# SCH_NeoGeo_chip_adapter_board_2026-08-28.net
KiCad netlist of a schematic drawn in EasyEDA
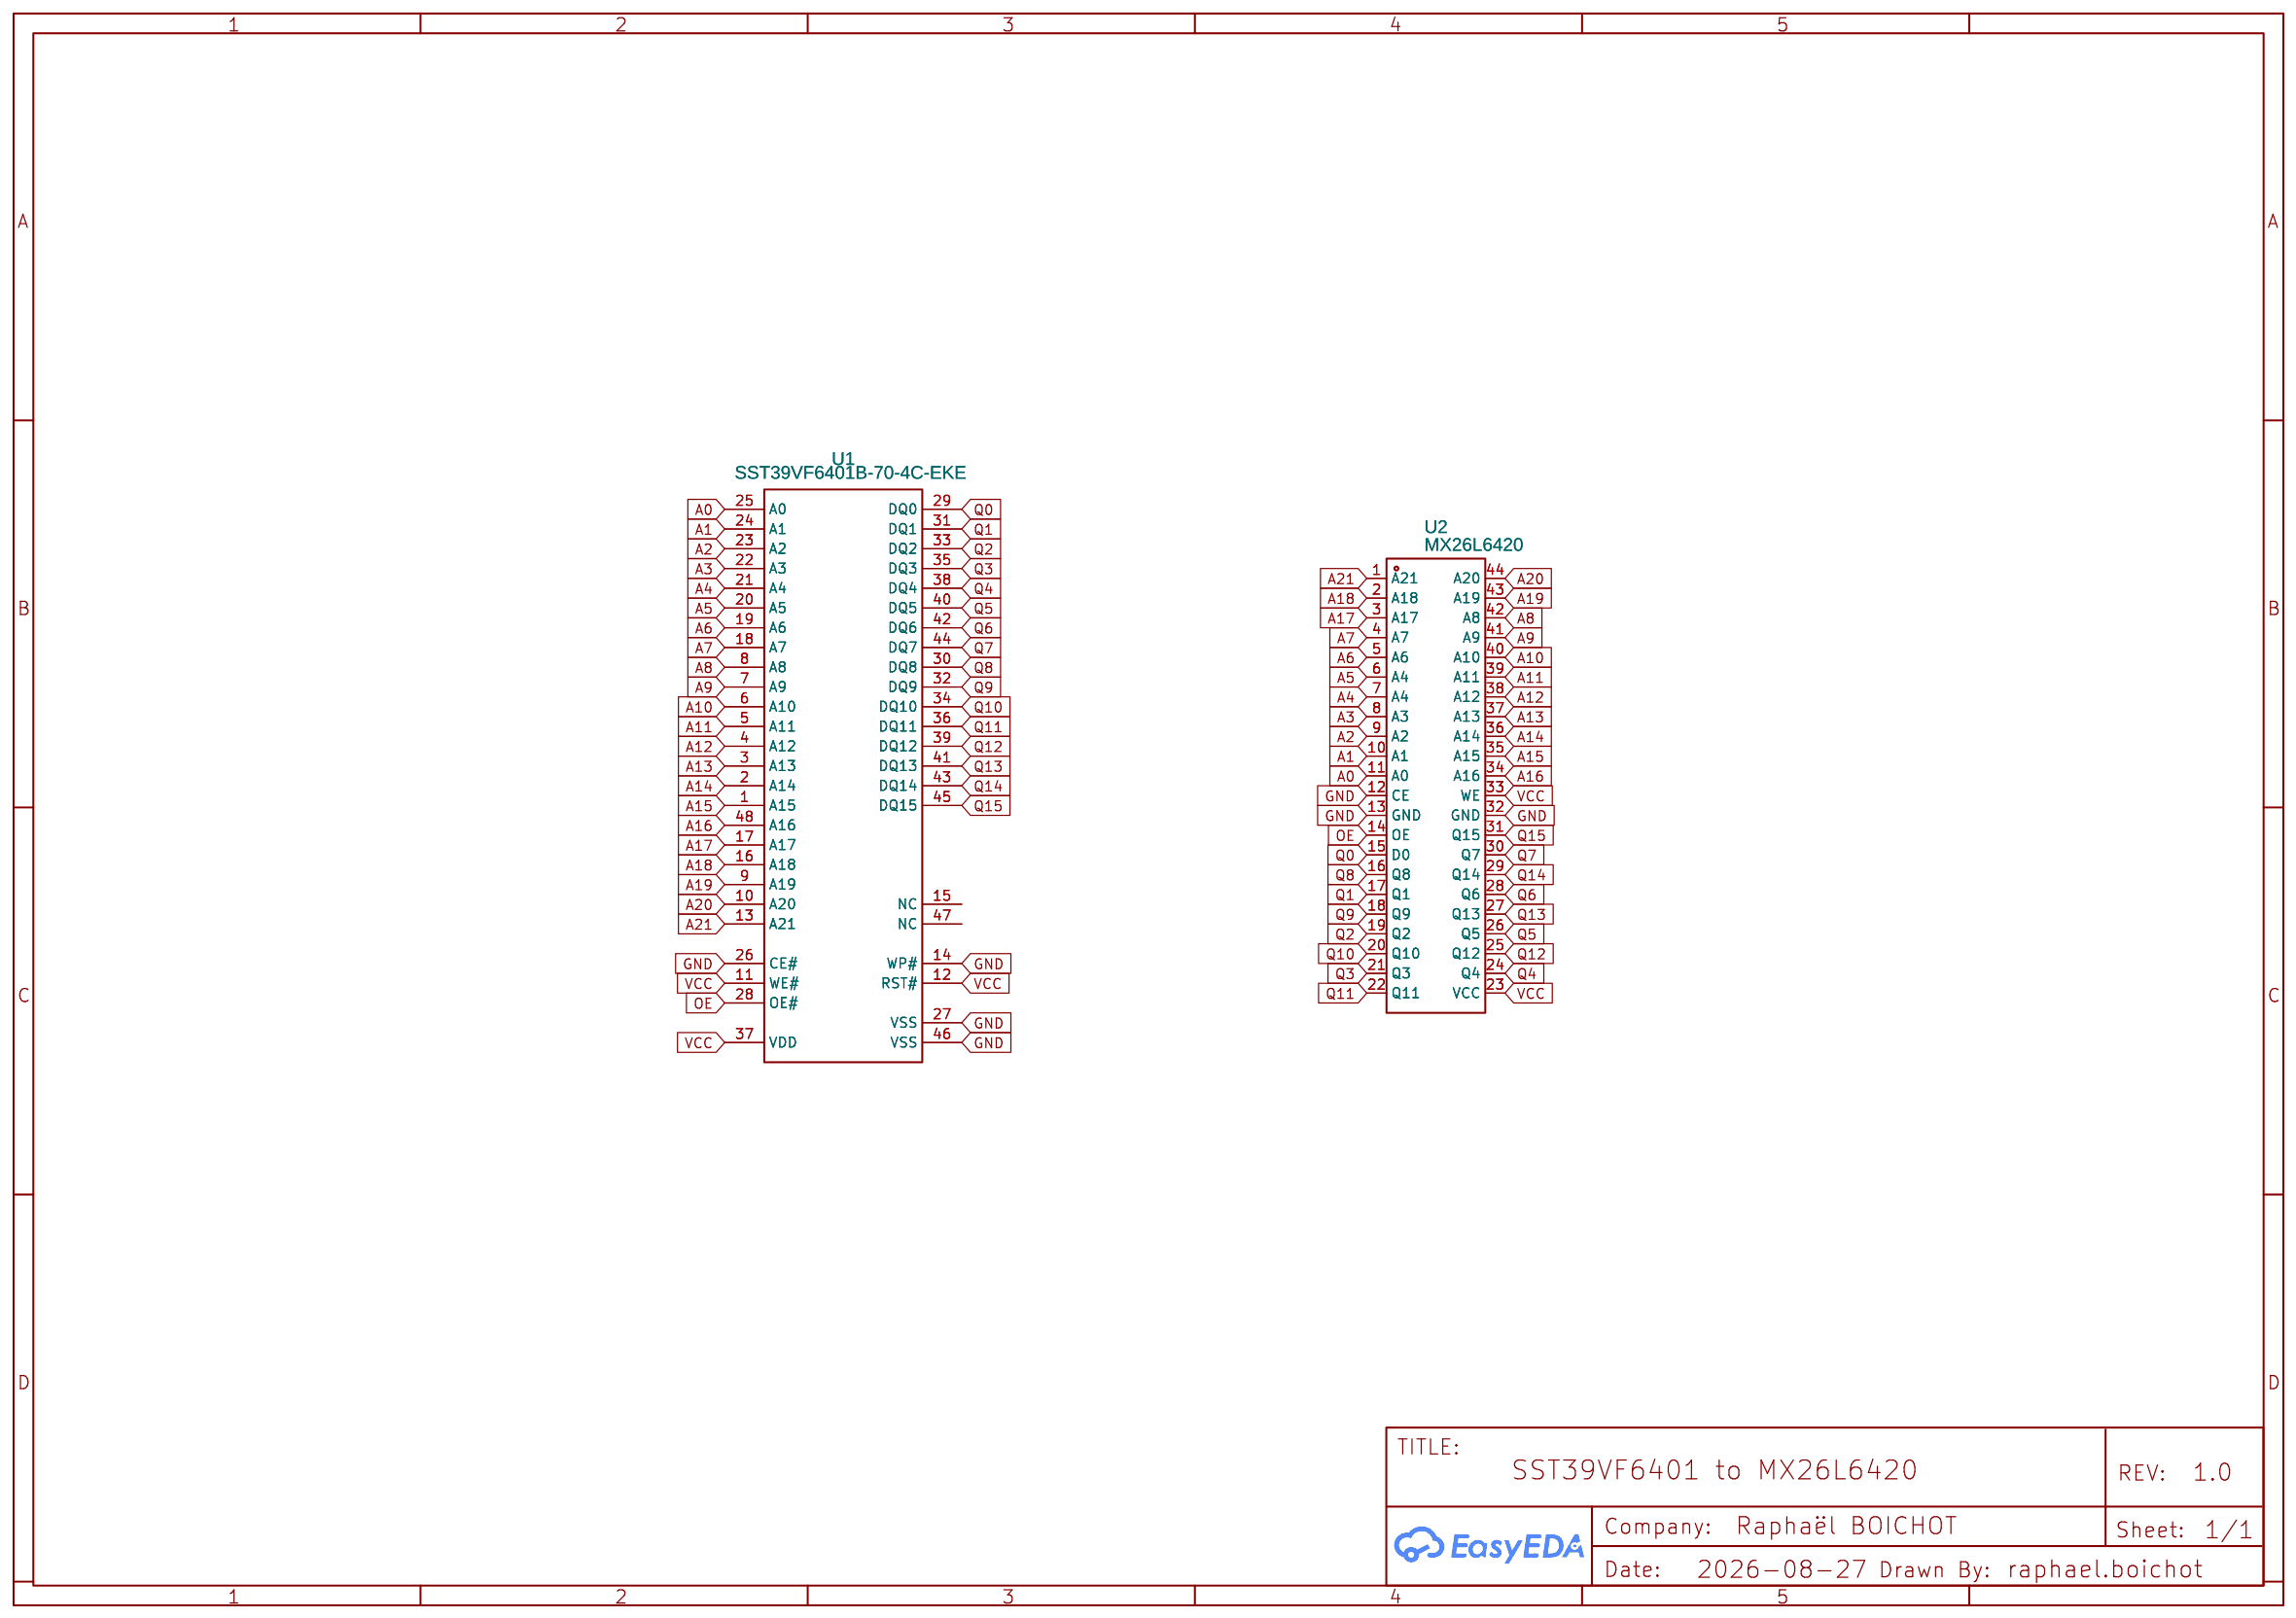
[diagram p0: schematic sheet]

(export (version "E")
  (design (tool "Eeschema 10.0.6"))
  (components
    (comp (ref "U1")
      (value "SST39VF6401B-70-4C-EKE")
      (fields (field (name "Manufacturer") "MICROCHIP(美国微芯)"))
      (libsource (lib "") (part "SST39VF6401B-70-4C-EKE"))
    )
    (comp (ref "U2")
      (value "MX26L6420")
      (fields (field (name "Manufacturer") "Macronix"))
      (libsource (lib "") (part "MX26L6420"))
    )
  )
  (nets
    (net (code "1") (name "A0") (class "Default")
      (node (ref "U1") (pin "25") (pinfunction "A0_25") (pintype "unspecified"))
      (node (ref "U2") (pin "11") (pinfunction "A0_11") (pintype "unspecified"))
    )
    (net (code "2") (name "A1") (class "Default")
      (node (ref "U1") (pin "24") (pinfunction "A1_24") (pintype "unspecified"))
      (node (ref "U2") (pin "10") (pinfunction "A1_10") (pintype "unspecified"))
    )
    (net (code "3") (name "A2") (class "Default")
      (node (ref "U1") (pin "23") (pinfunction "A2_23") (pintype "unspecified"))
      (node (ref "U2") (pin "9") (pinfunction "A2_9") (pintype "unspecified"))
    )
    (net (code "4") (name "A3") (class "Default")
      (node (ref "U1") (pin "22") (pinfunction "A3_22") (pintype "unspecified"))
      (node (ref "U2") (pin "8") (pinfunction "A3_8") (pintype "unspecified"))
    )
    (net (code "5") (name "A4") (class "Default")
      (node (ref "U1") (pin "21") (pinfunction "A4_21") (pintype "unspecified"))
      (node (ref "U2") (pin "7") (pinfunction "A4_7") (pintype "unspecified"))
    )
    (net (code "6") (name "A5") (class "Default")
      (node (ref "U1") (pin "20") (pinfunction "A5_20") (pintype "unspecified"))
      (node (ref "U2") (pin "6") (pinfunction "A4_6") (pintype "unspecified"))
    )
    (net (code "7") (name "A6") (class "Default")
      (node (ref "U1") (pin "19") (pinfunction "A6_19") (pintype "unspecified"))
      (node (ref "U2") (pin "5") (pinfunction "A6_5") (pintype "unspecified"))
    )
    (net (code "8") (name "A7") (class "Default")
      (node (ref "U1") (pin "18") (pinfunction "A7_18") (pintype "unspecified"))
      (node (ref "U2") (pin "4") (pinfunction "A7_4") (pintype "unspecified"))
    )
    (net (code "9") (name "A8") (class "Default")
      (node (ref "U1") (pin "8") (pinfunction "A8_8") (pintype "unspecified"))
      (node (ref "U2") (pin "42") (pinfunction "A8_42") (pintype "unspecified"))
    )
    (net (code "10") (name "A9") (class "Default")
      (node (ref "U1") (pin "7") (pinfunction "A9_7") (pintype "unspecified"))
      (node (ref "U2") (pin "41") (pinfunction "A9_41") (pintype "unspecified"))
    )
    (net (code "11") (name "A10") (class "Default")
      (node (ref "U1") (pin "6") (pinfunction "A10_6") (pintype "unspecified"))
      (node (ref "U2") (pin "40") (pinfunction "A10_40") (pintype "unspecified"))
    )
    (net (code "12") (name "A11") (class "Default")
      (node (ref "U1") (pin "5") (pinfunction "A11_5") (pintype "unspecified"))
      (node (ref "U2") (pin "39") (pinfunction "A11_39") (pintype "unspecified"))
    )
    (net (code "13") (name "A12") (class "Default")
      (node (ref "U1") (pin "4") (pinfunction "A12_4") (pintype "unspecified"))
      (node (ref "U2") (pin "38") (pinfunction "A12_38") (pintype "unspecified"))
    )
    (net (code "14") (name "A13") (class "Default")
      (node (ref "U1") (pin "3") (pinfunction "A13_3") (pintype "unspecified"))
      (node (ref "U2") (pin "37") (pinfunction "A13_37") (pintype "unspecified"))
    )
    (net (code "15") (name "A14") (class "Default")
      (node (ref "U1") (pin "2") (pinfunction "A14_2") (pintype "unspecified"))
      (node (ref "U2") (pin "36") (pinfunction "A14_36") (pintype "unspecified"))
    )
    (net (code "16") (name "A15") (class "Default")
      (node (ref "U1") (pin "1") (pinfunction "A15_1") (pintype "unspecified"))
      (node (ref "U2") (pin "35") (pinfunction "A15_35") (pintype "unspecified"))
    )
    (net (code "17") (name "A16") (class "Default")
      (node (ref "U1") (pin "48") (pinfunction "A16_48") (pintype "unspecified"))
      (node (ref "U2") (pin "34") (pinfunction "A16_34") (pintype "unspecified"))
    )
    (net (code "18") (name "A17") (class "Default")
      (node (ref "U1") (pin "17") (pinfunction "A17_17") (pintype "unspecified"))
      (node (ref "U2") (pin "3") (pinfunction "A17_3") (pintype "unspecified"))
    )
    (net (code "19") (name "A18") (class "Default")
      (node (ref "U1") (pin "16") (pinfunction "A18_16") (pintype "unspecified"))
      (node (ref "U2") (pin "2") (pinfunction "A18_2") (pintype "unspecified"))
    )
    (net (code "20") (name "A19") (class "Default")
      (node (ref "U1") (pin "9") (pinfunction "A19_9") (pintype "unspecified"))
      (node (ref "U2") (pin "43") (pinfunction "A19_43") (pintype "unspecified"))
    )
    (net (code "21") (name "A20") (class "Default")
      (node (ref "U1") (pin "10") (pinfunction "A20_10") (pintype "unspecified"))
      (node (ref "U2") (pin "44") (pinfunction "A20_44") (pintype "unspecified"))
    )
    (net (code "22") (name "A21") (class "Default")
      (node (ref "U1") (pin "13") (pinfunction "A21_13") (pintype "unspecified"))
      (node (ref "U2") (pin "1") (pinfunction "A21_1") (pintype "unspecified"))
    )
    (net (code "23") (name "GND") (class "Default")
      (node (ref "U1") (pin "14") (pinfunction "WP#_14") (pintype "unspecified"))
      (node (ref "U1") (pin "26") (pinfunction "CE#_26") (pintype "unspecified"))
      (node (ref "U1") (pin "27") (pinfunction "VSS_27") (pintype "passive"))
      (node (ref "U1") (pin "46") (pinfunction "VSS_46") (pintype "passive"))
      (node (ref "U2") (pin "12") (pinfunction "CE_12") (pintype "unspecified"))
      (node (ref "U2") (pin "13") (pinfunction "GND_13") (pintype "unspecified"))
      (node (ref "U2") (pin "32") (pinfunction "GND_32") (pintype "unspecified"))
    )
    (net (code "24") (name "OE") (class "Default")
      (node (ref "U1") (pin "28") (pinfunction "OE#_28") (pintype "unspecified"))
      (node (ref "U2") (pin "14") (pinfunction "OE_14") (pintype "unspecified"))
    )
    (net (code "25") (name "Q0") (class "Default")
      (node (ref "U1") (pin "29") (pinfunction "DQ0_29") (pintype "bidirectional"))
      (node (ref "U2") (pin "15") (pinfunction "D0_15") (pintype "unspecified"))
    )
    (net (code "26") (name "Q1") (class "Default")
      (node (ref "U1") (pin "31") (pinfunction "DQ1_31") (pintype "bidirectional"))
      (node (ref "U2") (pin "17") (pinfunction "Q1_17") (pintype "unspecified"))
    )
    (net (code "27") (name "Q2") (class "Default")
      (node (ref "U1") (pin "33") (pinfunction "DQ2_33") (pintype "bidirectional"))
      (node (ref "U2") (pin "19") (pinfunction "Q2_19") (pintype "unspecified"))
    )
    (net (code "28") (name "Q3") (class "Default")
      (node (ref "U1") (pin "35") (pinfunction "DQ3_35") (pintype "bidirectional"))
      (node (ref "U2") (pin "21") (pinfunction "Q3_21") (pintype "unspecified"))
    )
    (net (code "29") (name "Q4") (class "Default")
      (node (ref "U1") (pin "38") (pinfunction "DQ4_38") (pintype "bidirectional"))
      (node (ref "U2") (pin "24") (pinfunction "Q4_24") (pintype "unspecified"))
    )
    (net (code "30") (name "Q5") (class "Default")
      (node (ref "U1") (pin "40") (pinfunction "DQ5_40") (pintype "bidirectional"))
      (node (ref "U2") (pin "26") (pinfunction "Q5_26") (pintype "unspecified"))
    )
    (net (code "31") (name "Q6") (class "Default")
      (node (ref "U1") (pin "42") (pinfunction "DQ6_42") (pintype "bidirectional"))
      (node (ref "U2") (pin "28") (pinfunction "Q6_28") (pintype "unspecified"))
    )
    (net (code "32") (name "Q7") (class "Default")
      (node (ref "U1") (pin "44") (pinfunction "DQ7_44") (pintype "bidirectional"))
      (node (ref "U2") (pin "30") (pinfunction "Q7_30") (pintype "unspecified"))
    )
    (net (code "33") (name "Q8") (class "Default")
      (node (ref "U1") (pin "30") (pinfunction "DQ8_30") (pintype "bidirectional"))
      (node (ref "U2") (pin "16") (pinfunction "Q8_16") (pintype "unspecified"))
    )
    (net (code "34") (name "Q9") (class "Default")
      (node (ref "U1") (pin "32") (pinfunction "DQ9_32") (pintype "bidirectional"))
      (node (ref "U2") (pin "18") (pinfunction "Q9_18") (pintype "unspecified"))
    )
    (net (code "35") (name "Q10") (class "Default")
      (node (ref "U1") (pin "34") (pinfunction "DQ10_34") (pintype "bidirectional"))
      (node (ref "U2") (pin "20") (pinfunction "Q10_20") (pintype "unspecified"))
    )
    (net (code "36") (name "Q11") (class "Default")
      (node (ref "U1") (pin "36") (pinfunction "DQ11_36") (pintype "bidirectional"))
      (node (ref "U2") (pin "22") (pinfunction "Q11_22") (pintype "unspecified"))
    )
    (net (code "37") (name "Q12") (class "Default")
      (node (ref "U1") (pin "39") (pinfunction "DQ12_39") (pintype "bidirectional"))
      (node (ref "U2") (pin "25") (pinfunction "Q12_25") (pintype "unspecified"))
    )
    (net (code "38") (name "Q13") (class "Default")
      (node (ref "U1") (pin "41") (pinfunction "DQ13_41") (pintype "bidirectional"))
      (node (ref "U2") (pin "27") (pinfunction "Q13_27") (pintype "unspecified"))
    )
    (net (code "39") (name "Q14") (class "Default")
      (node (ref "U1") (pin "43") (pinfunction "DQ14_43") (pintype "bidirectional"))
      (node (ref "U2") (pin "29") (pinfunction "Q14_29") (pintype "unspecified"))
    )
    (net (code "40") (name "Q15") (class "Default")
      (node (ref "U1") (pin "45") (pinfunction "DQ15_45") (pintype "bidirectional"))
      (node (ref "U2") (pin "31") (pinfunction "Q15_31") (pintype "unspecified"))
    )
    (net (code "41") (name "VCC") (class "Default")
      (node (ref "U1") (pin "11") (pinfunction "WE#_11") (pintype "unspecified"))
      (node (ref "U1") (pin "12") (pinfunction "RST#_12") (pintype "unspecified"))
      (node (ref "U1") (pin "37") (pinfunction "VDD_37") (pintype "passive"))
      (node (ref "U2") (pin "23") (pinfunction "VCC_23") (pintype "unspecified"))
      (node (ref "U2") (pin "33") (pinfunction "WE_33") (pintype "unspecified"))
    )
    (net (code "42") (name "unconnected-(U1-NC-Pad15)") (class "Default")
      (node (ref "U1") (pin "15") (pinfunction "NC_15") (pintype "unspecified"))
    )
    (net (code "43") (name "unconnected-(U1-NC-Pad47)") (class "Default")
      (node (ref "U1") (pin "47") (pinfunction "NC_47") (pintype "unspecified"))
    )
  )
)
